# dsPIC33CK.net
KiCad netlist of a schematic drawn in Altium Designer
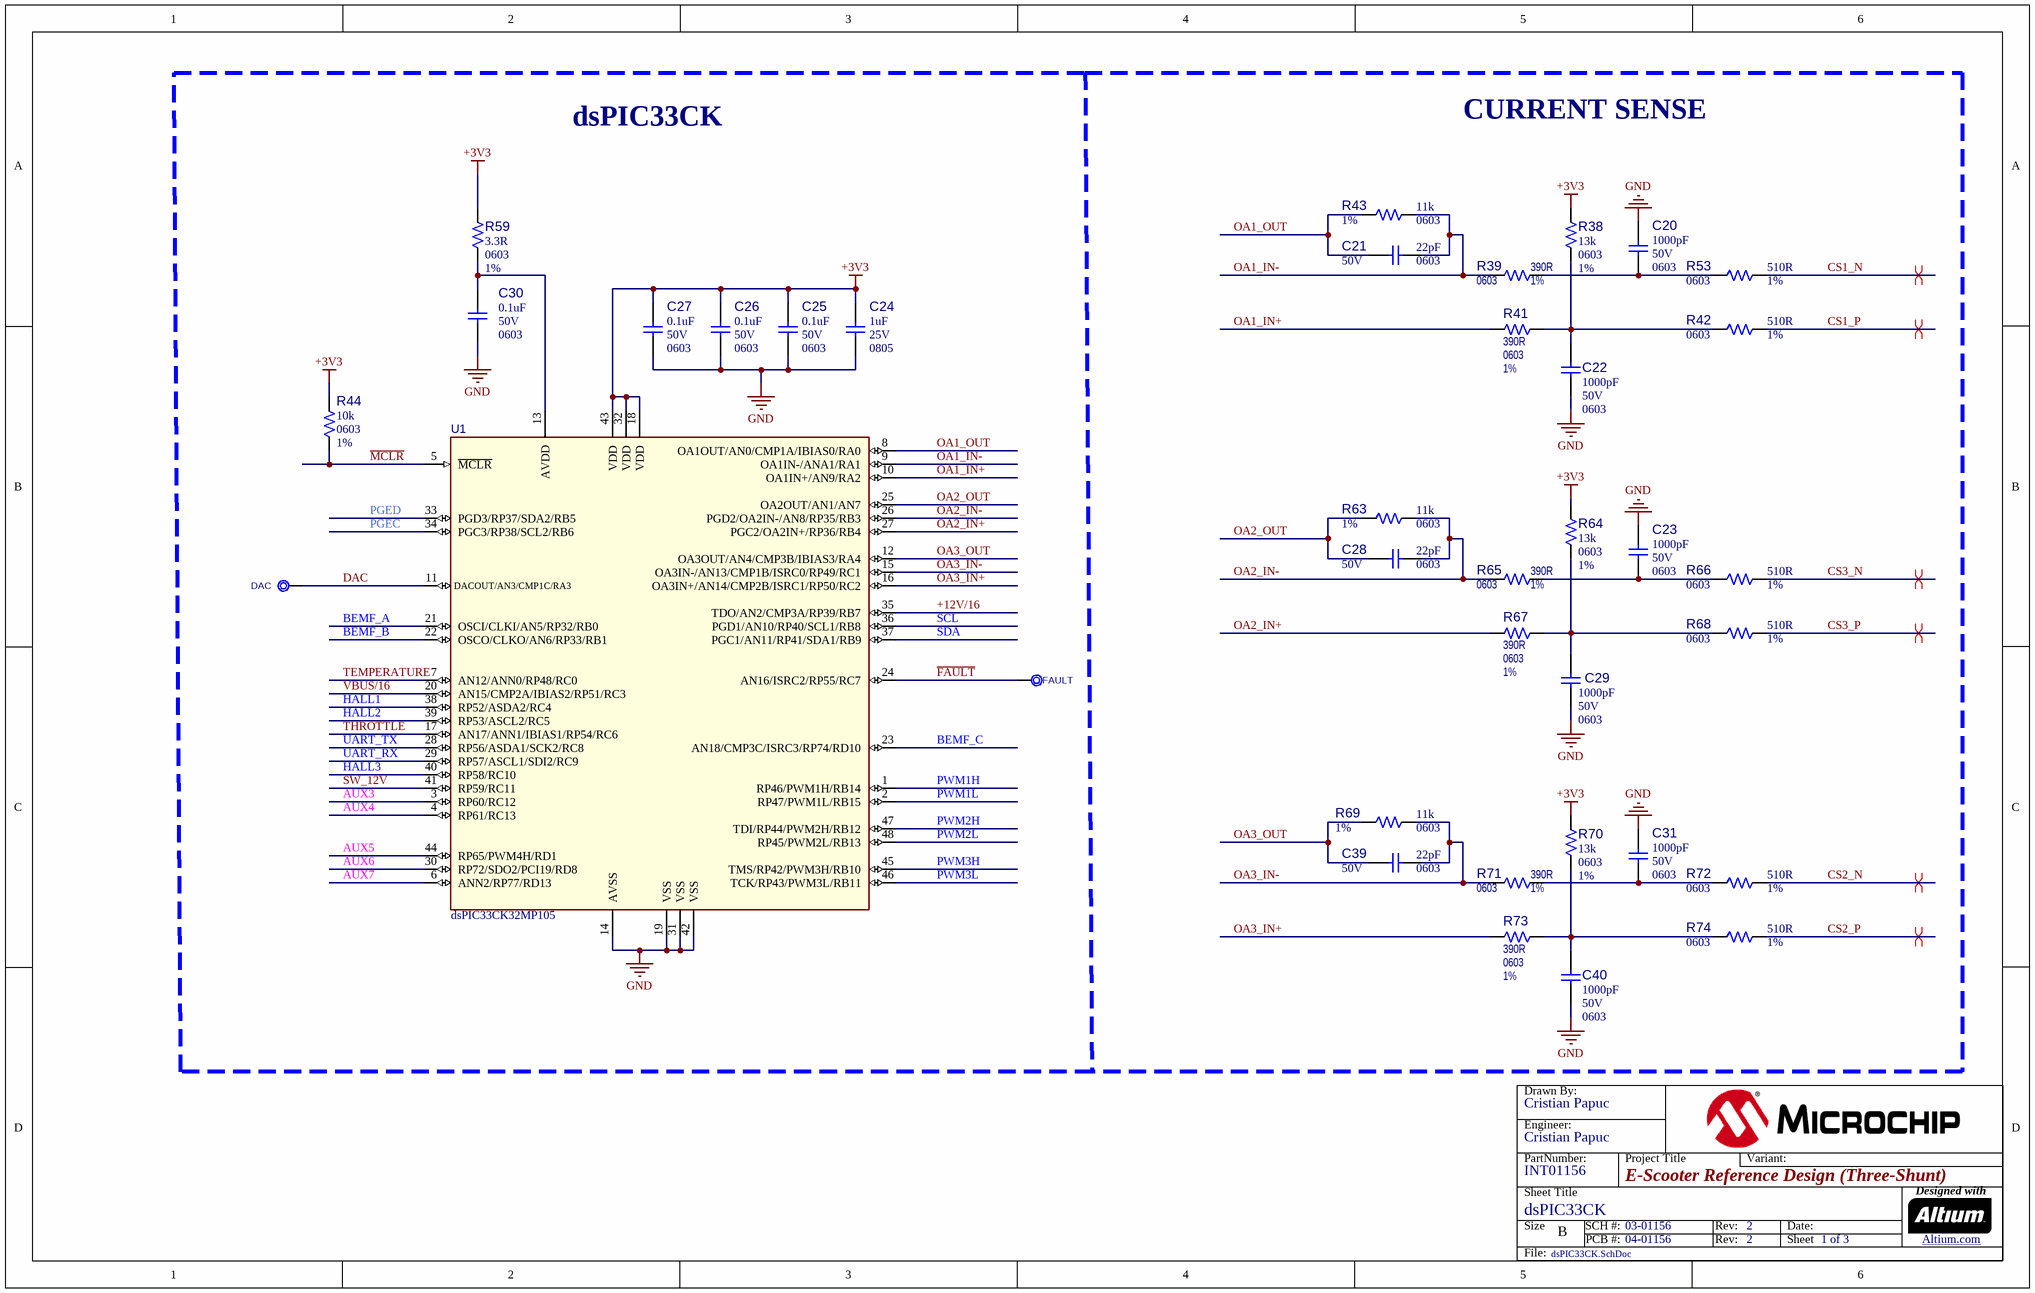
[diagram p0: dsPIC33CK.SchDoc]

(export (version "E")
  (design (tool "Eeschema 10.0.6"))
  (components
    (comp (ref "C20")
      (value "1000pF")
      (footprint "CAP_C_0603")
      (description "Capacitor")
      (fields
        (field (name "VOLTAGE") "50V")
        (field (name "PACKAGE") "0603")
        (field (name "TOLERANCE") "10%")
        (field (name "Comment") "Capacitor NP")
      )
      (libsource (lib "MCHP-CDB") (part "Capacitor NP"))
    )
    (comp (ref "C21")
      (value "22pF")
      (footprint "CAP_C_0603")
      (description "Capacitor")
      (fields
        (field (name "VOLTAGE") "50V")
        (field (name "PACKAGE") "0603")
        (field (name "TOLERANCE") "5%")
        (field (name "Comment") "Capacitor NP")
      )
      (libsource (lib "MCHP-CDB") (part "Capacitor NP"))
    )
    (comp (ref "C22")
      (value "1000pF")
      (footprint "CAP_C_0603")
      (description "Capacitor")
      (fields
        (field (name "VOLTAGE") "50V")
        (field (name "PACKAGE") "0603")
        (field (name "TOLERANCE") "10%")
        (field (name "Comment") "Capacitor NP")
      )
      (libsource (lib "MCHP-CDB") (part "Capacitor NP"))
    )
    (comp (ref "C23")
      (value "1000pF")
      (footprint "CAP_C_0603")
      (description "Capacitor")
      (fields
        (field (name "VOLTAGE") "50V")
        (field (name "PACKAGE") "0603")
        (field (name "TOLERANCE") "10%")
        (field (name "Comment") "Capacitor NP")
      )
      (libsource (lib "MCHP-CDB") (part "Capacitor NP"))
    )
    (comp (ref "C24")
      (value "1uF")
      (footprint "CAP_C_0805")
      (description "Capacitor")
      (fields
        (field (name "VOLTAGE") "25V")
        (field (name "PACKAGE") "0805")
        (field (name "TOLERANCE") "10%")
        (field (name "Comment") "Capacitor NP")
        (field (name "OWNER") "Tad Ahlvers")
      )
      (libsource (lib "") (part "Capacitor NP_1"))
    )
    (comp (ref "C25")
      (value "0.1uF")
      (footprint "CAP_C_0603")
      (description "Capacitor")
      (fields
        (field (name "VOLTAGE") "50V")
        (field (name "PACKAGE") "0603")
        (field (name "TOLERANCE") "10%")
        (field (name "Comment") "Capacitor NP")
        (field (name "OWNER") "Sam Charles")
      )
      (libsource (lib "") (part "Capacitor NP_1"))
    )
    (comp (ref "C26")
      (value "0.1uF")
      (footprint "CAP_C_0603")
      (description "Capacitor")
      (fields
        (field (name "VOLTAGE") "50V")
        (field (name "PACKAGE") "0603")
        (field (name "TOLERANCE") "10%")
        (field (name "Comment") "Capacitor NP")
        (field (name "OWNER") "Sam Charles")
      )
      (libsource (lib "") (part "Capacitor NP_1"))
    )
    (comp (ref "C27")
      (value "0.1uF")
      (footprint "CAP_C_0603")
      (description "Capacitor")
      (fields
        (field (name "VOLTAGE") "50V")
        (field (name "PACKAGE") "0603")
        (field (name "TOLERANCE") "10%")
        (field (name "Comment") "Capacitor NP")
        (field (name "OWNER") "Sam Charles")
      )
      (libsource (lib "") (part "Capacitor NP_1"))
    )
    (comp (ref "C28")
      (value "22pF")
      (footprint "CAP_C_0603")
      (description "Capacitor")
      (fields
        (field (name "VOLTAGE") "50V")
        (field (name "PACKAGE") "0603")
        (field (name "TOLERANCE") "5%")
        (field (name "Comment") "Capacitor NP")
      )
      (libsource (lib "MCHP-CDB") (part "Capacitor NP"))
    )
    (comp (ref "C29")
      (value "1000pF")
      (footprint "CAP_C_0603")
      (description "Capacitor")
      (fields
        (field (name "VOLTAGE") "50V")
        (field (name "PACKAGE") "0603")
        (field (name "TOLERANCE") "10%")
        (field (name "Comment") "Capacitor NP")
      )
      (libsource (lib "MCHP-CDB") (part "Capacitor NP"))
    )
    (comp (ref "C30")
      (value "0.1uF")
      (footprint "CAP_C_0603")
      (description "Capacitor")
      (fields
        (field (name "VOLTAGE") "50V")
        (field (name "PACKAGE") "0603")
        (field (name "TOLERANCE") "10%")
        (field (name "Comment") "Capacitor NP")
        (field (name "OWNER") "Sam Charles")
      )
      (libsource (lib "") (part "Capacitor NP_1"))
    )
    (comp (ref "C31")
      (value "1000pF")
      (footprint "CAP_C_0603")
      (description "Capacitor")
      (fields
        (field (name "VOLTAGE") "50V")
        (field (name "PACKAGE") "0603")
        (field (name "TOLERANCE") "10%")
        (field (name "Comment") "Capacitor NP")
      )
      (libsource (lib "MCHP-CDB") (part "Capacitor NP"))
    )
    (comp (ref "C39")
      (value "22pF")
      (footprint "CAP_C_0603")
      (description "Capacitor")
      (fields
        (field (name "VOLTAGE") "50V")
        (field (name "PACKAGE") "0603")
        (field (name "TOLERANCE") "5%")
        (field (name "Comment") "Capacitor NP")
      )
      (libsource (lib "MCHP-CDB") (part "Capacitor NP"))
    )
    (comp (ref "C40")
      (value "1000pF")
      (footprint "CAP_C_0603")
      (description "Capacitor")
      (fields
        (field (name "VOLTAGE") "50V")
        (field (name "PACKAGE") "0603")
        (field (name "TOLERANCE") "10%")
        (field (name "Comment") "Capacitor NP")
      )
      (libsource (lib "MCHP-CDB") (part "Capacitor NP"))
    )
    (comp (ref "DAC")
      (value "DAC")
      (footprint "TP_1.2x0.7")
      (description "Test Point")
      (fields (field (name "OWNER") "Bogdan P (M91398)"))
      (libsource (lib "MCHP-CDB") (part "Test Point No BOM"))
    )
    (comp (ref "R38")
      (value "13k")
      (footprint "RES_C_0603")
      (description "Resistor")
      (fields
        (field (name "PACKAGE") "0603")
        (field (name "TOLERANCE") "1%")
        (field (name "VOLTAGE") "75V")
        (field (name "POWER") "1/10W")
        (field (name "OWNER") "Mihai T(M91442)")
      )
      (libsource (lib "MCHP-CDB") (part "Resistor"))
    )
    (comp (ref "R39")
      (value "390R")
      (footprint "RES_C_0603")
      (description "Resistor")
      (fields
        (field (name "PACKAGE") "0603")
        (field (name "TOLERANCE") "1%")
        (field (name "VOLTAGE") "75V")
        (field (name "POWER") "1/10W")
        (field (name "OWNER") "Bogdan P (M91398)")
      )
      (libsource (lib "MCHP-CDB") (part "Resistor"))
    )
    (comp (ref "R41")
      (value "390R")
      (footprint "RES_C_0603")
      (description "Resistor")
      (fields
        (field (name "PACKAGE") "0603")
        (field (name "TOLERANCE") "1%")
        (field (name "VOLTAGE") "75V")
        (field (name "POWER") "1/10W")
        (field (name "OWNER") "Bogdan P (M91398)")
      )
      (libsource (lib "MCHP-CDB") (part "Resistor"))
    )
    (comp (ref "R42")
      (value "510R")
      (footprint "RES_C_0603")
      (description "Resistor")
      (fields
        (field (name "PACKAGE") "0603")
        (field (name "TOLERANCE") "1%")
        (field (name "VOLTAGE") "50V")
        (field (name "POWER") "1/10W")
      )
      (libsource (lib "MCHP-CDB") (part "Resistor"))
    )
    (comp (ref "R43")
      (value "11k")
      (footprint "RES_C_0603")
      (description "Resistor")
      (fields
        (field (name "PACKAGE") "0603")
        (field (name "TOLERANCE") "1%")
        (field (name "VOLTAGE") "75V")
        (field (name "POWER") "1/10W")
      )
      (libsource (lib "MCHP-CDB") (part "Resistor"))
    )
    (comp (ref "R44")
      (value "10k")
      (footprint "RES_C_0603")
      (description "Resistor")
      (fields (field (name "PACKAGE") "0603") (field (name "TOLERANCE") "1%") (field (name "POWER") "1/10W"))
      (libsource (lib "MCHP-CDB") (part "Resistor"))
    )
    (comp (ref "R53")
      (value "510R")
      (footprint "RES_C_0603")
      (description "Resistor")
      (fields
        (field (name "PACKAGE") "0603")
        (field (name "TOLERANCE") "1%")
        (field (name "VOLTAGE") "50V")
        (field (name "POWER") "1/10W")
      )
      (libsource (lib "MCHP-CDB") (part "Resistor"))
    )
    (comp (ref "R59")
      (value "3.3R")
      (footprint "RES_C_0603")
      (description "Resistor")
      (fields
        (field (name "PACKAGE") "0603")
        (field (name "TOLERANCE") "1%")
        (field (name "POWER") "1/10W")
        (field (name "OWNER") "Tad Ahlvers")
      )
      (libsource (lib "MCHP-CDB") (part "Resistor"))
    )
    (comp (ref "R63")
      (value "11k")
      (footprint "RES_C_0603")
      (description "Resistor")
      (fields
        (field (name "PACKAGE") "0603")
        (field (name "TOLERANCE") "1%")
        (field (name "VOLTAGE") "75V")
        (field (name "POWER") "1/10W")
      )
      (libsource (lib "MCHP-CDB") (part "Resistor"))
    )
    (comp (ref "R64")
      (value "13k")
      (footprint "RES_C_0603")
      (description "Resistor")
      (fields
        (field (name "PACKAGE") "0603")
        (field (name "TOLERANCE") "1%")
        (field (name "VOLTAGE") "75V")
        (field (name "POWER") "1/10W")
        (field (name "OWNER") "Mihai T(M91442)")
      )
      (libsource (lib "MCHP-CDB") (part "Resistor"))
    )
    (comp (ref "R65")
      (value "390R")
      (footprint "RES_C_0603")
      (description "Resistor")
      (fields
        (field (name "PACKAGE") "0603")
        (field (name "TOLERANCE") "1%")
        (field (name "VOLTAGE") "75V")
        (field (name "POWER") "1/10W")
        (field (name "OWNER") "Bogdan P (M91398)")
      )
      (libsource (lib "MCHP-CDB") (part "Resistor"))
    )
    (comp (ref "R66")
      (value "510R")
      (footprint "RES_C_0603")
      (description "Resistor")
      (fields
        (field (name "PACKAGE") "0603")
        (field (name "TOLERANCE") "1%")
        (field (name "VOLTAGE") "50V")
        (field (name "POWER") "1/10W")
      )
      (libsource (lib "MCHP-CDB") (part "Resistor"))
    )
    (comp (ref "R67")
      (value "390R")
      (footprint "RES_C_0603")
      (description "Resistor")
      (fields
        (field (name "PACKAGE") "0603")
        (field (name "TOLERANCE") "1%")
        (field (name "VOLTAGE") "75V")
        (field (name "POWER") "1/10W")
        (field (name "OWNER") "Bogdan P (M91398)")
      )
      (libsource (lib "MCHP-CDB") (part "Resistor"))
    )
    (comp (ref "R68")
      (value "510R")
      (footprint "RES_C_0603")
      (description "Resistor")
      (fields
        (field (name "PACKAGE") "0603")
        (field (name "TOLERANCE") "1%")
        (field (name "VOLTAGE") "50V")
        (field (name "POWER") "1/10W")
      )
      (libsource (lib "MCHP-CDB") (part "Resistor"))
    )
    (comp (ref "R69")
      (value "11k")
      (footprint "RES_C_0603")
      (description "Resistor")
      (fields
        (field (name "PACKAGE") "0603")
        (field (name "TOLERANCE") "1%")
        (field (name "VOLTAGE") "75V")
        (field (name "POWER") "1/10W")
      )
      (libsource (lib "MCHP-CDB") (part "Resistor"))
    )
    (comp (ref "R70")
      (value "13k")
      (footprint "RES_C_0603")
      (description "Resistor")
      (fields
        (field (name "PACKAGE") "0603")
        (field (name "TOLERANCE") "1%")
        (field (name "VOLTAGE") "75V")
        (field (name "POWER") "1/10W")
        (field (name "OWNER") "Mihai T(M91442)")
      )
      (libsource (lib "MCHP-CDB") (part "Resistor"))
    )
    (comp (ref "R71")
      (value "390R")
      (footprint "RES_C_0603")
      (description "Resistor")
      (fields
        (field (name "PACKAGE") "0603")
        (field (name "TOLERANCE") "1%")
        (field (name "VOLTAGE") "75V")
        (field (name "POWER") "1/10W")
        (field (name "OWNER") "Bogdan P (M91398)")
      )
      (libsource (lib "MCHP-CDB") (part "Resistor"))
    )
    (comp (ref "R72")
      (value "510R")
      (footprint "RES_C_0603")
      (description "Resistor")
      (fields
        (field (name "PACKAGE") "0603")
        (field (name "TOLERANCE") "1%")
        (field (name "VOLTAGE") "50V")
        (field (name "POWER") "1/10W")
      )
      (libsource (lib "MCHP-CDB") (part "Resistor"))
    )
    (comp (ref "R73")
      (value "390R")
      (footprint "RES_C_0603")
      (description "Resistor")
      (fields
        (field (name "PACKAGE") "0603")
        (field (name "TOLERANCE") "1%")
        (field (name "VOLTAGE") "75V")
        (field (name "POWER") "1/10W")
        (field (name "OWNER") "Bogdan P (M91398)")
      )
      (libsource (lib "MCHP-CDB") (part "Resistor"))
    )
    (comp (ref "R74")
      (value "510R")
      (footprint "RES_C_0603")
      (description "Resistor")
      (fields
        (field (name "PACKAGE") "0603")
        (field (name "TOLERANCE") "1%")
        (field (name "VOLTAGE") "50V")
        (field (name "POWER") "1/10W")
      )
      (libsource (lib "MCHP-CDB") (part "Resistor"))
    )
    (comp (ref "TP1")
      (value "FAULT")
      (footprint "TP_1.2x0.7")
      (description "Test Point")
      (fields (field (name "OWNER") "Bogdan P (M91398)"))
      (libsource (lib "MCHP-CDB") (part "Test Point No BOM"))
    )
    (comp (ref "U1")
      (value "dsPIC33CK32MP105")
      (footprint "TQFP-48_7x7")
      (fields (field (name "OWNER") "Octavian Stroe"))
      (libsource (lib "MCHP-CDB") (part "dsPIC33CK32MP105 TQFP-48"))
    )
  )
  (nets
    (net (code "1") (name "+3V3") (class "Default")
      (node (ref "C24") (pin "2") (pinfunction "2_2") (pintype "passive"))
      (node (ref "C25") (pin "2") (pinfunction "2_2") (pintype "passive"))
      (node (ref "C26") (pin "2") (pinfunction "2_2") (pintype "passive"))
      (node (ref "C27") (pin "2") (pinfunction "2_2") (pintype "passive"))
      (node (ref "R38") (pin "1") (pinfunction "1_1") (pintype "passive"))
      (node (ref "R44") (pin "2") (pinfunction "2_2") (pintype "passive"))
      (node (ref "R59") (pin "2") (pinfunction "2_2") (pintype "passive"))
      (node (ref "R64") (pin "1") (pinfunction "1_1") (pintype "passive"))
      (node (ref "R70") (pin "1") (pinfunction "1_1") (pintype "passive"))
      (node (ref "U1") (pin "18") (pinfunction "VDD_18") (pintype "power_in"))
      (node (ref "U1") (pin "32") (pinfunction "VDD_32") (pintype "power_in"))
      (node (ref "U1") (pin "43") (pinfunction "VDD_43") (pintype "power_in"))
    )
    (net (code "2") (name "/+12V{slash}16") (class "Default")
      (node (ref "U1") (pin "35") (pinfunction "TDO/AN2/CMP3A/RP39/RB7_35") (pintype "bidirectional"))
    )
    (net (code "3") (name "/AUX3") (class "Default")
      (node (ref "U1") (pin "3") (pinfunction "RP60/RC12_3") (pintype "bidirectional"))
    )
    (net (code "4") (name "/AUX4") (class "Default")
      (node (ref "U1") (pin "4") (pinfunction "RP61/RC13_4") (pintype "bidirectional"))
    )
    (net (code "5") (name "/AUX5") (class "Default")
      (node (ref "U1") (pin "44") (pinfunction "RP65/PWM4H/RD1_44") (pintype "bidirectional"))
    )
    (net (code "6") (name "/AUX6") (class "Default")
      (node (ref "U1") (pin "30") (pinfunction "RP72/SDO2/PCI19/RD8_30") (pintype "bidirectional"))
    )
    (net (code "7") (name "/AUX7") (class "Default")
      (node (ref "U1") (pin "6") (pinfunction "ANN2/RP77/RD13_6") (pintype "bidirectional"))
    )
    (net (code "8") (name "/BEMF_A") (class "Default")
      (node (ref "U1") (pin "21") (pinfunction "OSCI/CLKI/AN5/RP32/RB0_21") (pintype "bidirectional"))
    )
    (net (code "9") (name "/BEMF_B") (class "Default")
      (node (ref "U1") (pin "22") (pinfunction "OSCO/CLKO/AN6/RP33/RB1_22") (pintype "bidirectional"))
    )
    (net (code "10") (name "/BEMF_C") (class "Default")
      (node (ref "U1") (pin "23") (pinfunction "AN18/CMP3C/ISRC3/RP74/RD10_23") (pintype "bidirectional"))
    )
    (net (code "11") (name "/CS1_N") (class "Default")
      (node (ref "R53") (pin "2") (pinfunction "2_2") (pintype "passive"))
    )
    (net (code "12") (name "/CS1_P") (class "Default")
      (node (ref "R42") (pin "2") (pinfunction "2_2") (pintype "passive"))
    )
    (net (code "13") (name "/CS2_N") (class "Default")
      (node (ref "R72") (pin "2") (pinfunction "2_2") (pintype "passive"))
    )
    (net (code "14") (name "/CS2_P") (class "Default")
      (node (ref "R74") (pin "2") (pinfunction "2_2") (pintype "passive"))
    )
    (net (code "15") (name "/CS3_N") (class "Default")
      (node (ref "R66") (pin "2") (pinfunction "2_2") (pintype "passive"))
    )
    (net (code "16") (name "/CS3_P") (class "Default")
      (node (ref "R68") (pin "2") (pinfunction "2_2") (pintype "passive"))
    )
    (net (code "17") (name "/DAC") (class "Default")
      (node (ref "DAC") (pin "1") (pinfunction "1_1") (pintype "passive"))
      (node (ref "U1") (pin "11") (pinfunction "DACOUT/AN3/CMP1C/RA3_11") (pintype "bidirectional"))
    )
    (net (code "18") (name "/FAULT") (class "Default")
      (node (ref "TP1") (pin "1") (pinfunction "1_1") (pintype "passive"))
      (node (ref "U1") (pin "24") (pinfunction "AN16/ISRC2/RP55/RC7_24") (pintype "bidirectional"))
    )
    (net (code "19") (name "/HALL1") (class "Default")
      (node (ref "U1") (pin "38") (pinfunction "RP52/ASDA2/RC4_38") (pintype "bidirectional"))
    )
    (net (code "20") (name "/HALL2") (class "Default")
      (node (ref "U1") (pin "39") (pinfunction "RP53/ASCL2/RC5_39") (pintype "bidirectional"))
    )
    (net (code "21") (name "/HALL3") (class "Default")
      (node (ref "U1") (pin "40") (pinfunction "RP58/RC10_40") (pintype "bidirectional"))
    )
    (net (code "22") (name "/MCLR") (class "Default")
      (node (ref "R44") (pin "1") (pinfunction "1_1") (pintype "passive"))
      (node (ref "U1") (pin "5") (pinfunction "MCLR_5") (pintype "input"))
    )
    (net (code "23") (name "/OA1_IN+") (class "Default")
      (node (ref "R41") (pin "1") (pinfunction "1_1") (pintype "passive"))
      (node (ref "U1") (pin "10") (pinfunction "OA1IN+/AN9/RA2_10") (pintype "bidirectional"))
    )
    (net (code "24") (name "/OA1_IN-") (class "Default")
      (node (ref "C21") (pin "1") (pinfunction "1_1") (pintype "passive"))
      (node (ref "R39") (pin "1") (pinfunction "1_1") (pintype "passive"))
      (node (ref "R43") (pin "1") (pinfunction "1_1") (pintype "passive"))
      (node (ref "U1") (pin "9") (pinfunction "OA1IN-/ANA1/RA1_9") (pintype "bidirectional"))
    )
    (net (code "25") (name "/OA1_OUT") (class "Default")
      (node (ref "C21") (pin "2") (pinfunction "2_2") (pintype "passive"))
      (node (ref "R43") (pin "2") (pinfunction "2_2") (pintype "passive"))
      (node (ref "U1") (pin "8") (pinfunction "OA1OUT/AN0/CMP1A/IBIAS0/RA0_8") (pintype "bidirectional"))
    )
    (net (code "26") (name "/OA2_IN+") (class "Default")
      (node (ref "R67") (pin "1") (pinfunction "1_1") (pintype "passive"))
      (node (ref "U1") (pin "27") (pinfunction "PGC2/OA2IN+/RP36/RB4_27") (pintype "bidirectional"))
    )
    (net (code "27") (name "/OA2_IN-") (class "Default")
      (node (ref "C28") (pin "1") (pinfunction "1_1") (pintype "passive"))
      (node (ref "R63") (pin "1") (pinfunction "1_1") (pintype "passive"))
      (node (ref "R65") (pin "1") (pinfunction "1_1") (pintype "passive"))
      (node (ref "U1") (pin "26") (pinfunction "PGD2/OA2IN-/AN8/RP35/RB3_26") (pintype "bidirectional"))
    )
    (net (code "28") (name "/OA2_OUT") (class "Default")
      (node (ref "C28") (pin "2") (pinfunction "2_2") (pintype "passive"))
      (node (ref "R63") (pin "2") (pinfunction "2_2") (pintype "passive"))
      (node (ref "U1") (pin "25") (pinfunction "OA2OUT/AN1/AN7_25") (pintype "bidirectional"))
    )
    (net (code "29") (name "/OA3_IN+") (class "Default")
      (node (ref "R73") (pin "1") (pinfunction "1_1") (pintype "passive"))
      (node (ref "U1") (pin "16") (pinfunction "OA3IN+/AN14/CMP2B/ISRC1/RP50/RC2_16") (pintype "bidirectional"))
    )
    (net (code "30") (name "/OA3_IN-") (class "Default")
      (node (ref "C39") (pin "1") (pinfunction "1_1") (pintype "passive"))
      (node (ref "R69") (pin "1") (pinfunction "1_1") (pintype "passive"))
      (node (ref "R71") (pin "1") (pinfunction "1_1") (pintype "passive"))
      (node (ref "U1") (pin "15") (pinfunction "OA3IN-/AN13/CMP1B/ISRC0/RP49/RC1_15") (pintype "bidirectional"))
    )
    (net (code "31") (name "/OA3_OUT") (class "Default")
      (node (ref "C39") (pin "2") (pinfunction "2_2") (pintype "passive"))
      (node (ref "R69") (pin "2") (pinfunction "2_2") (pintype "passive"))
      (node (ref "U1") (pin "12") (pinfunction "OA3OUT/AN4/CMP3B/IBIAS3/RA4_12") (pintype "bidirectional"))
    )
    (net (code "32") (name "/PGEC") (class "Default")
      (node (ref "U1") (pin "34") (pinfunction "PGC3/RP38/SCL2/RB6_34") (pintype "bidirectional"))
    )
    (net (code "33") (name "/PGED") (class "Default")
      (node (ref "U1") (pin "33") (pinfunction "PGD3/RP37/SDA2/RB5_33") (pintype "bidirectional"))
    )
    (net (code "34") (name "/PWM1H") (class "Default")
      (node (ref "U1") (pin "1") (pinfunction "RP46/PWM1H/RB14_1") (pintype "bidirectional"))
    )
    (net (code "35") (name "/PWM1L") (class "Default")
      (node (ref "U1") (pin "2") (pinfunction "RP47/PWM1L/RB15_2") (pintype "bidirectional"))
    )
    (net (code "36") (name "/PWM2H") (class "Default")
      (node (ref "U1") (pin "47") (pinfunction "TDI/RP44/PWM2H/RB12_47") (pintype "bidirectional"))
    )
    (net (code "37") (name "/PWM2L") (class "Default")
      (node (ref "U1") (pin "48") (pinfunction "RP45/PWM2L/RB13_48") (pintype "bidirectional"))
    )
    (net (code "38") (name "/PWM3H") (class "Default")
      (node (ref "U1") (pin "45") (pinfunction "TMS/RP42/PWM3H/RB10_45") (pintype "bidirectional"))
    )
    (net (code "39") (name "/PWM3L") (class "Default")
      (node (ref "U1") (pin "46") (pinfunction "TCK/RP43/PWM3L/RB11_46") (pintype "bidirectional"))
    )
    (net (code "40") (name "/SCL") (class "Default")
      (node (ref "U1") (pin "36") (pinfunction "PGD1/AN10/RP40/SCL1/RB8_36") (pintype "bidirectional"))
    )
    (net (code "41") (name "/SDA") (class "Default")
      (node (ref "U1") (pin "37") (pinfunction "PGC1/AN11/RP41/SDA1/RB9_37") (pintype "bidirectional"))
    )
    (net (code "42") (name "/SW_12V") (class "Default")
      (node (ref "U1") (pin "41") (pinfunction "RP59/RC11_41") (pintype "bidirectional"))
    )
    (net (code "43") (name "/TEMPERATURE") (class "Default")
      (node (ref "U1") (pin "7") (pinfunction "AN12/ANN0/RP48/RC0_7") (pintype "bidirectional"))
    )
    (net (code "44") (name "/THROTTLE") (class "Default")
      (node (ref "U1") (pin "17") (pinfunction "AN17/ANN1/IBIAS1/RP54/RC6_17") (pintype "bidirectional"))
    )
    (net (code "45") (name "/UART_RX") (class "Default")
      (node (ref "U1") (pin "29") (pinfunction "RP57/ASCL1/SDI2/RC9_29") (pintype "bidirectional"))
    )
    (net (code "46") (name "/UART_TX") (class "Default")
      (node (ref "U1") (pin "28") (pinfunction "RP56/ASDA1/SCK2/RC8_28") (pintype "bidirectional"))
    )
    (net (code "47") (name "/VBUS{slash}16") (class "Default")
      (node (ref "U1") (pin "20") (pinfunction "AN15/CMP2A/IBIAS2/RP51/RC3_20") (pintype "bidirectional"))
    )
    (net (code "48") (name "GND") (class "Default")
      (node (ref "C20") (pin "2") (pinfunction "2_2") (pintype "passive"))
      (node (ref "C22") (pin "1") (pinfunction "1_1") (pintype "passive"))
      (node (ref "C23") (pin "2") (pinfunction "2_2") (pintype "passive"))
      (node (ref "C24") (pin "1") (pinfunction "1_1") (pintype "passive"))
      (node (ref "C25") (pin "1") (pinfunction "1_1") (pintype "passive"))
      (node (ref "C26") (pin "1") (pinfunction "1_1") (pintype "passive"))
      (node (ref "C27") (pin "1") (pinfunction "1_1") (pintype "passive"))
      (node (ref "C29") (pin "1") (pinfunction "1_1") (pintype "passive"))
      (node (ref "C30") (pin "1") (pinfunction "1_1") (pintype "passive"))
      (node (ref "C31") (pin "2") (pinfunction "2_2") (pintype "passive"))
      (node (ref "C40") (pin "1") (pinfunction "1_1") (pintype "passive"))
      (node (ref "U1") (pin "14") (pinfunction "AVSS_14") (pintype "power_in"))
      (node (ref "U1") (pin "19") (pinfunction "VSS_19") (pintype "power_in"))
      (node (ref "U1") (pin "31") (pinfunction "VSS_31") (pintype "power_in"))
      (node (ref "U1") (pin "42") (pinfunction "VSS_42") (pintype "power_in"))
    )
    (net (code "49") (name "Net-(C20-Pad1)") (class "Default")
      (node (ref "C20") (pin "1") (pinfunction "1_1") (pintype "passive"))
      (node (ref "R39") (pin "2") (pinfunction "2_2") (pintype "passive"))
      (node (ref "R53") (pin "1") (pinfunction "1_1") (pintype "passive"))
    )
    (net (code "50") (name "Net-(C22-Pad2)") (class "Default")
      (node (ref "C22") (pin "2") (pinfunction "2_2") (pintype "passive"))
      (node (ref "R38") (pin "2") (pinfunction "2_2") (pintype "passive"))
      (node (ref "R41") (pin "2") (pinfunction "2_2") (pintype "passive"))
      (node (ref "R42") (pin "1") (pinfunction "1_1") (pintype "passive"))
    )
    (net (code "51") (name "Net-(C23-Pad1)") (class "Default")
      (node (ref "C23") (pin "1") (pinfunction "1_1") (pintype "passive"))
      (node (ref "R65") (pin "2") (pinfunction "2_2") (pintype "passive"))
      (node (ref "R66") (pin "1") (pinfunction "1_1") (pintype "passive"))
    )
    (net (code "52") (name "Net-(C29-Pad2)") (class "Default")
      (node (ref "C29") (pin "2") (pinfunction "2_2") (pintype "passive"))
      (node (ref "R64") (pin "2") (pinfunction "2_2") (pintype "passive"))
      (node (ref "R67") (pin "2") (pinfunction "2_2") (pintype "passive"))
      (node (ref "R68") (pin "1") (pinfunction "1_1") (pintype "passive"))
    )
    (net (code "53") (name "Net-(C31-Pad1)") (class "Default")
      (node (ref "C31") (pin "1") (pinfunction "1_1") (pintype "passive"))
      (node (ref "R71") (pin "2") (pinfunction "2_2") (pintype "passive"))
      (node (ref "R72") (pin "1") (pinfunction "1_1") (pintype "passive"))
    )
    (net (code "54") (name "Net-(C40-Pad2)") (class "Default")
      (node (ref "C40") (pin "2") (pinfunction "2_2") (pintype "passive"))
      (node (ref "R70") (pin "2") (pinfunction "2_2") (pintype "passive"))
      (node (ref "R73") (pin "2") (pinfunction "2_2") (pintype "passive"))
      (node (ref "R74") (pin "1") (pinfunction "1_1") (pintype "passive"))
    )
    (net (code "55") (name "Net-(U1-AVDD)") (class "Default")
      (node (ref "C30") (pin "2") (pinfunction "2_2") (pintype "passive"))
      (node (ref "R59") (pin "1") (pinfunction "1_1") (pintype "passive"))
      (node (ref "U1") (pin "13") (pinfunction "AVDD_13") (pintype "power_in"))
    )
  )
)
